# Current_Sense.net
KiCad netlist of a schematic drawn in Altium Designer
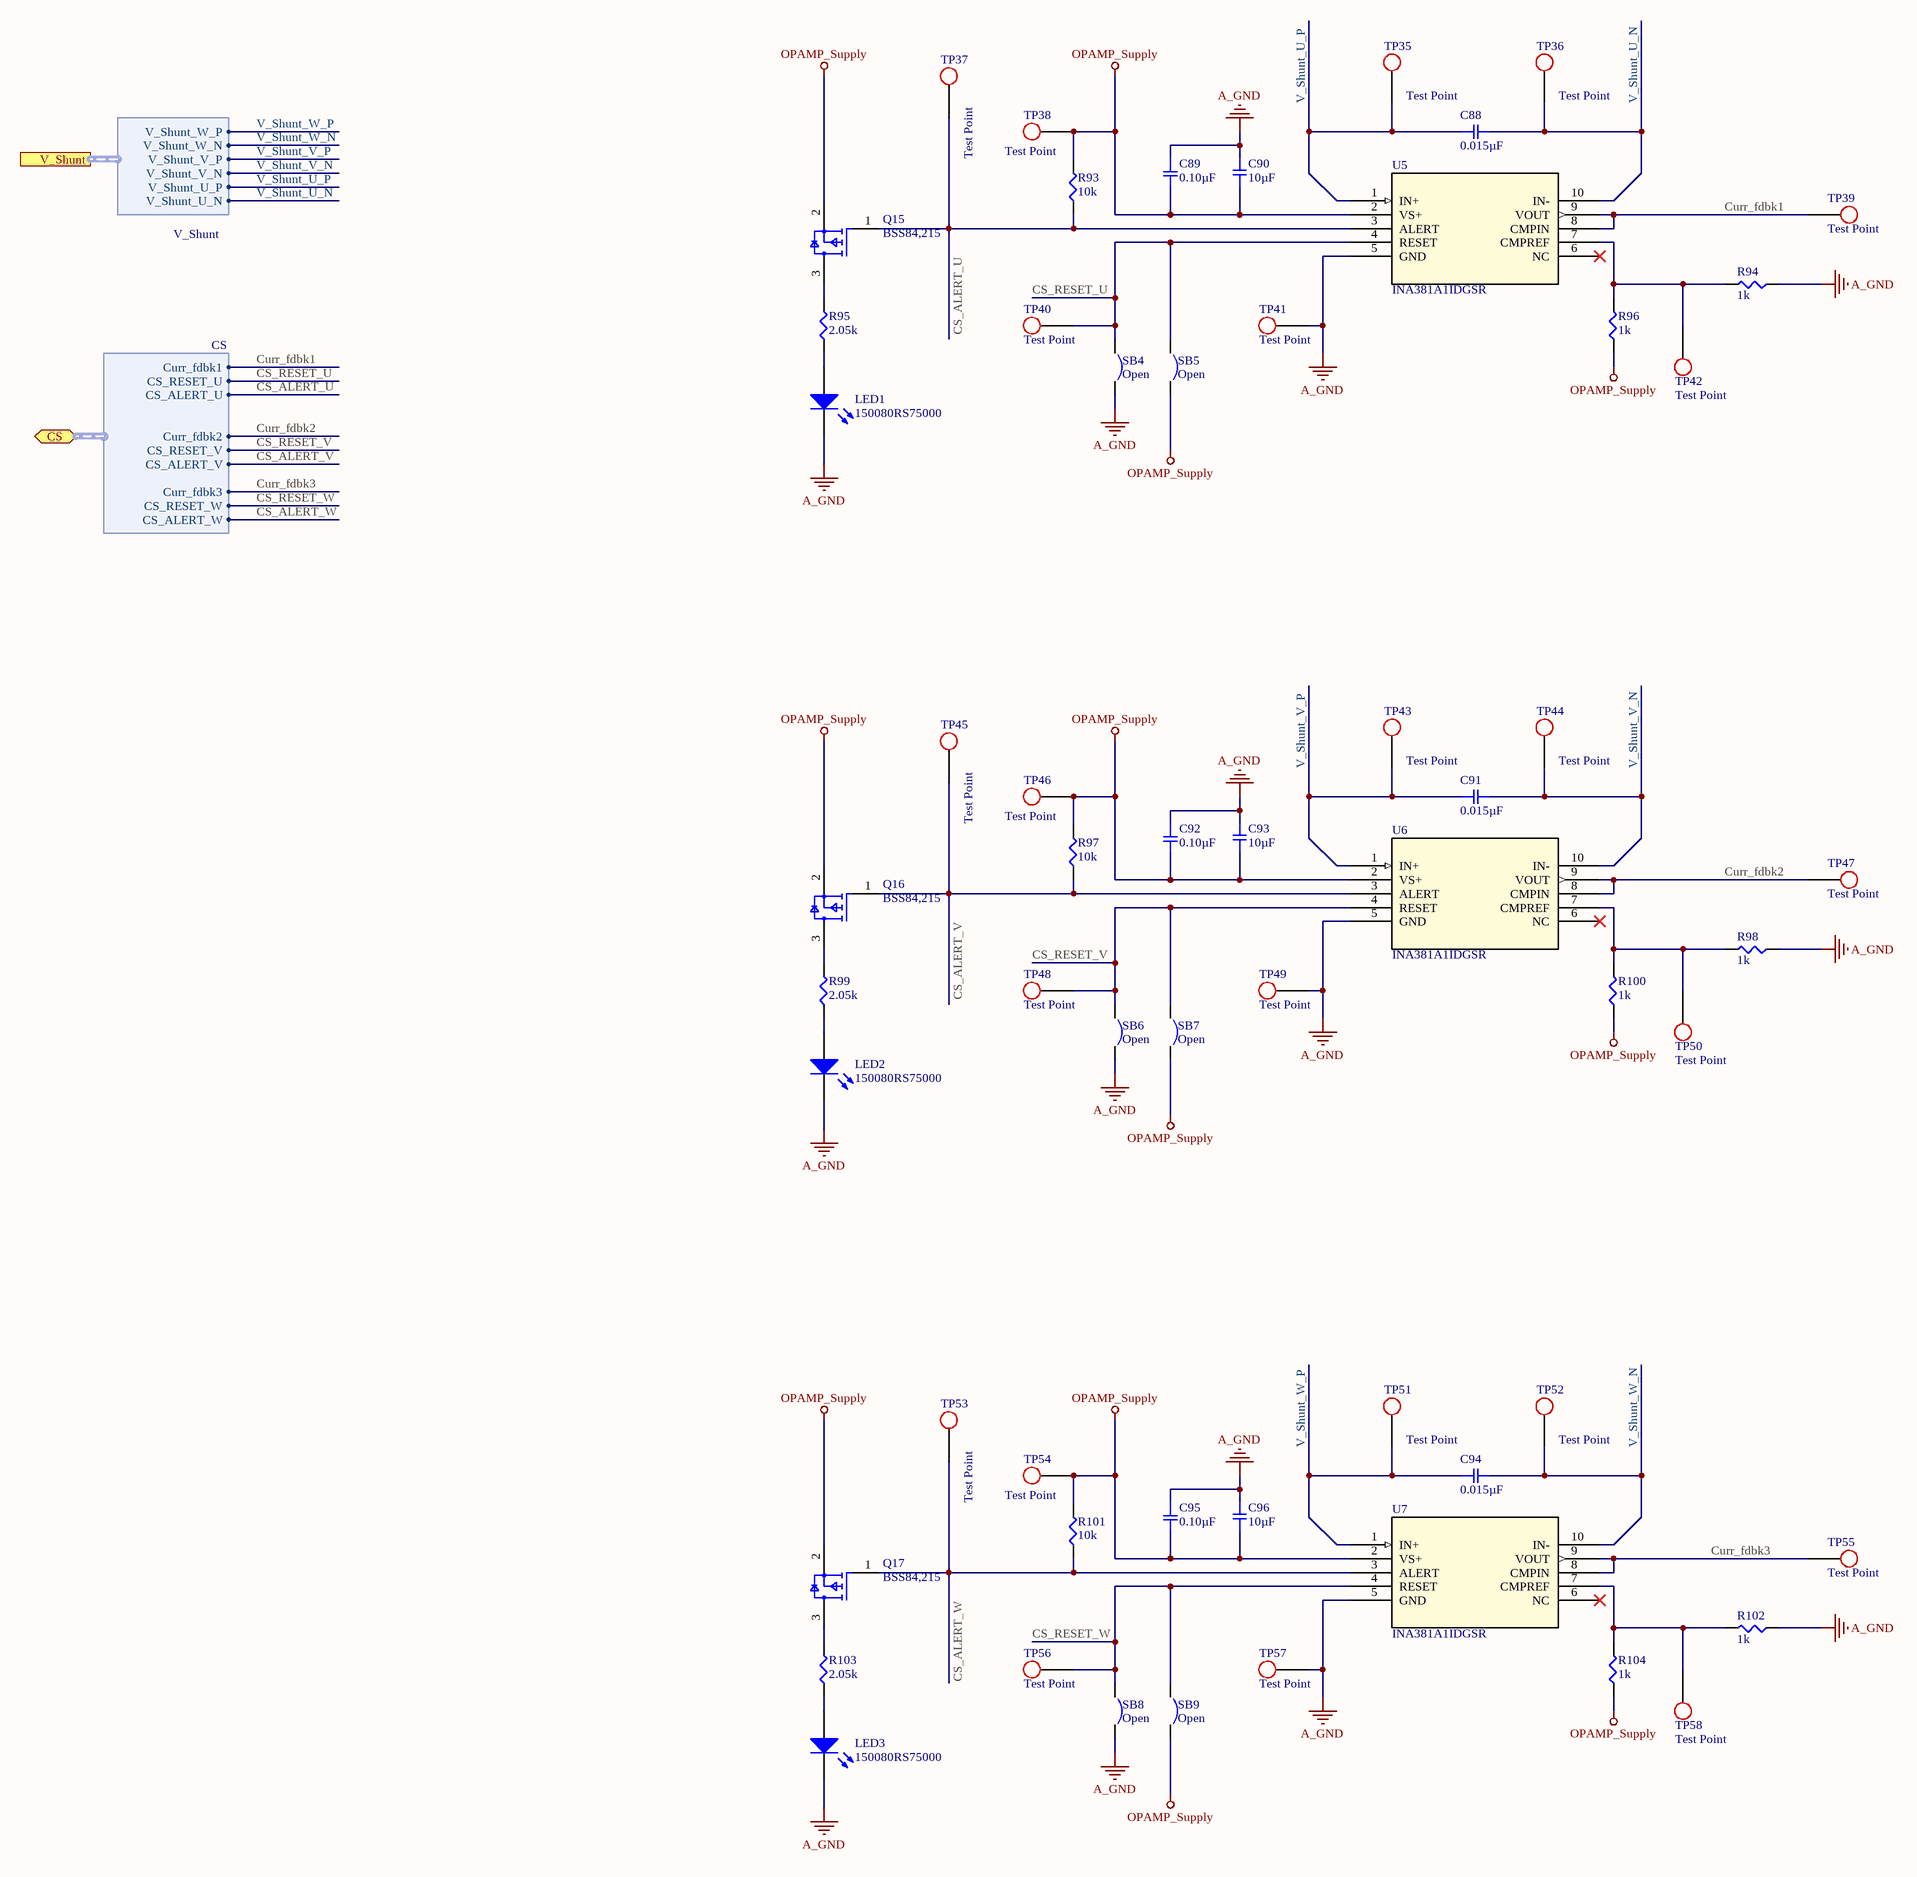
[diagram p0: Current Sense.SchDoc]

(export (version "E")
  (design (tool "Eeschema 10.0.6"))
  (components
    (comp (ref "C88")
      (value "0.015µF")
      (footprint "SMD-0603C")
      (description "CAP CER 0.015UF 100V X7R 0603")
      (fields
        (field (name "DIGI-KEY PART NUMBER") "490-5770-1-ND")
        (field (name "PART NUMBER") "GCJ188R72A153KA01D")
      )
      (libsource (lib "capacitor_murata_0603") (part "GCJ188R72A153KA01D"))
    )
    (comp (ref "C89")
      (value "0.10µF")
      (footprint "SMD-0805C")
      (description "CAP CER 0.1UF 50V X7R 0805")
      (fields
        (field (name "DIGI-KEY PART NUMBER") "490-8049-1-ND")
        (field (name "PART NUMBER") "GCM21BR71H104KA37K")
      )
      (libsource (lib "capacitor_murata_0805") (part "GCM21BR71H104KA37K"))
    )
    (comp (ref "C90")
      (value "10µF")
      (footprint "SMD-1206C")
      (description "CAP CER 10UF 25V X7R 1206")
      (fields
        (field (name "DIGI-KEY PART NUMBER") "490-10940-1-ND")
        (field (name "PART NUMBER") "GRJ31CR71E106KE11L")
      )
      (libsource (lib "capacitor_murata_1206") (part "GRJ31CR71E106KE11L"))
    )
    (comp (ref "C91")
      (value "0.015µF")
      (footprint "SMD-0603C")
      (description "CAP CER 0.015UF 100V X7R 0603")
      (fields
        (field (name "DIGI-KEY PART NUMBER") "490-5770-1-ND")
        (field (name "PART NUMBER") "GCJ188R72A153KA01D")
      )
      (libsource (lib "capacitor_murata_0603") (part "GCJ188R72A153KA01D"))
    )
    (comp (ref "C92")
      (value "0.10µF")
      (footprint "SMD-0805C")
      (description "CAP CER 0.1UF 50V X7R 0805")
      (fields
        (field (name "DIGI-KEY PART NUMBER") "490-8049-1-ND")
        (field (name "PART NUMBER") "GCM21BR71H104KA37K")
      )
      (libsource (lib "capacitor_murata_0805") (part "GCM21BR71H104KA37K"))
    )
    (comp (ref "C93")
      (value "10µF")
      (footprint "SMD-1206C")
      (description "CAP CER 10UF 25V X7R 1206")
      (fields
        (field (name "DIGI-KEY PART NUMBER") "490-10940-1-ND")
        (field (name "PART NUMBER") "GRJ31CR71E106KE11L")
      )
      (libsource (lib "capacitor_murata_1206") (part "GRJ31CR71E106KE11L"))
    )
    (comp (ref "C94")
      (value "0.015µF")
      (footprint "SMD-0603C")
      (description "CAP CER 0.015UF 100V X7R 0603")
      (fields
        (field (name "DIGI-KEY PART NUMBER") "490-5770-1-ND")
        (field (name "PART NUMBER") "GCJ188R72A153KA01D")
      )
      (libsource (lib "capacitor_murata_0603") (part "GCJ188R72A153KA01D"))
    )
    (comp (ref "C95")
      (value "0.10µF")
      (footprint "SMD-0805C")
      (description "CAP CER 0.1UF 50V X7R 0805")
      (fields
        (field (name "DIGI-KEY PART NUMBER") "490-8049-1-ND")
        (field (name "PART NUMBER") "GCM21BR71H104KA37K")
      )
      (libsource (lib "capacitor_murata_0805") (part "GCM21BR71H104KA37K"))
    )
    (comp (ref "C96")
      (value "10µF")
      (footprint "SMD-1206C")
      (description "CAP CER 10UF 25V X7R 1206")
      (fields
        (field (name "DIGI-KEY PART NUMBER") "490-10940-1-ND")
        (field (name "PART NUMBER") "GRJ31CR71E106KE11L")
      )
      (libsource (lib "capacitor_murata_1206") (part "GRJ31CR71E106KE11L"))
    )
    (comp (ref "LED1")
      (value "150080RS75000")
      (footprint "0805_A")
      (description "SMD mono-color Chip LED, WL-SMCW, Red")
      (libsource (lib "WL-SMCW SMD chip LED top view mono-color waterclear") (part "150080RS75000"))
    )
    (comp (ref "LED2")
      (value "150080RS75000")
      (footprint "0805_A")
      (description "SMD mono-color Chip LED, WL-SMCW, Red")
      (libsource (lib "WL-SMCW SMD chip LED top view mono-color waterclear") (part "150080RS75000"))
    )
    (comp (ref "LED3")
      (value "150080RS75000")
      (footprint "0805_A")
      (description "SMD mono-color Chip LED, WL-SMCW, Red")
      (libsource (lib "WL-SMCW SMD chip LED top view mono-color waterclear") (part "150080RS75000"))
    )
    (comp (ref "Q15")
      (value "BSS84,215")
      (footprint "FP-SOT23-MFG")
      (description "P-Channel 50V 130mA (Ta) 250mW (Tc) Surface Mount TO-236AB")
      (fields (field (name "OCTOPART") "https://octopart.com/bss84%2C215-nexperia-78739375"))
      (libsource (lib "Altium Content Vault") (part "2a9bca3c979204b206c86ddeb8c1a69"))
    )
    (comp (ref "Q16")
      (value "BSS84,215")
      (footprint "FP-SOT23-MFG")
      (description "P-Channel 50V 130mA (Ta) 250mW (Tc) Surface Mount TO-236AB")
      (fields (field (name "OCTOPART") "https://octopart.com/bss84%2C215-nexperia-78739375"))
      (libsource (lib "Altium Content Vault") (part "2a9bca3c979204b206c86ddeb8c1a69"))
    )
    (comp (ref "Q17")
      (value "BSS84,215")
      (footprint "FP-SOT23-MFG")
      (description "P-Channel 50V 130mA (Ta) 250mW (Tc) Surface Mount TO-236AB")
      (fields (field (name "OCTOPART") "https://octopart.com/bss84%2C215-nexperia-78739375"))
      (libsource (lib "Altium Content Vault") (part "2a9bca3c979204b206c86ddeb8c1a69"))
    )
    (comp (ref "R93")
      (value "10k")
      (footprint "SMD-0603-RES")
      (description "RES SMD 10K OHM 1% 1/10W 0603")
      (fields
        (field (name "PART NUMBER") "ERJ-3EKF1002V")
        (field (name "DIGI-KEY PART NUMBER") "P10.0KHCT-ND")
      )
      (libsource (lib "Panasonic_ERJ_0603") (part "ERJ-3EKF1002V"))
    )
    (comp (ref "R94")
      (value "1k")
      (footprint "SMD-0603-RES")
      (description "RES SMD 1K OHM 1% 1/10W 0603")
      (fields
        (field (name "PART NUMBER") "ERJ-3EKF1001V")
        (field (name "DIGI-KEY PART NUMBER") "P1.00KHCT-ND")
      )
      (libsource (lib "Panasonic_ERJ_0603") (part "ERJ-3EKF1001V"))
    )
    (comp (ref "R95")
      (value "2.05k")
      (footprint "SMD-0603-RES")
      (description "RES SMD 2.05K OHM 1% 1/10W 0603")
      (fields
        (field (name "PART NUMBER") "ERJ-3EKF2051V")
        (field (name "DIGI-KEY PART NUMBER") "P2.05KHCT-ND")
      )
      (libsource (lib "Panasonic_ERJ_0603") (part "ERJ-3EKF2051V"))
    )
    (comp (ref "R96")
      (value "1k")
      (footprint "SMD-0603-RES")
      (description "RES SMD 1K OHM 1% 1/10W 0603")
      (fields
        (field (name "PART NUMBER") "ERJ-3EKF1001V")
        (field (name "DIGI-KEY PART NUMBER") "P1.00KHCT-ND")
      )
      (libsource (lib "Panasonic_ERJ_0603") (part "ERJ-3EKF1001V"))
    )
    (comp (ref "R97")
      (value "10k")
      (footprint "SMD-0603-RES")
      (description "RES SMD 10K OHM 1% 1/10W 0603")
      (fields
        (field (name "PART NUMBER") "ERJ-3EKF1002V")
        (field (name "DIGI-KEY PART NUMBER") "P10.0KHCT-ND")
      )
      (libsource (lib "Panasonic_ERJ_0603") (part "ERJ-3EKF1002V"))
    )
    (comp (ref "R98")
      (value "1k")
      (footprint "SMD-0603-RES")
      (description "RES SMD 1K OHM 1% 1/10W 0603")
      (fields
        (field (name "PART NUMBER") "ERJ-3EKF1001V")
        (field (name "DIGI-KEY PART NUMBER") "P1.00KHCT-ND")
      )
      (libsource (lib "Panasonic_ERJ_0603") (part "ERJ-3EKF1001V"))
    )
    (comp (ref "R99")
      (value "2.05k")
      (footprint "SMD-0603-RES")
      (description "RES SMD 2.05K OHM 1% 1/10W 0603")
      (fields
        (field (name "PART NUMBER") "ERJ-3EKF2051V")
        (field (name "DIGI-KEY PART NUMBER") "P2.05KHCT-ND")
      )
      (libsource (lib "Panasonic_ERJ_0603") (part "ERJ-3EKF2051V"))
    )
    (comp (ref "R100")
      (value "1k")
      (footprint "SMD-0603-RES")
      (description "RES SMD 1K OHM 1% 1/10W 0603")
      (fields
        (field (name "PART NUMBER") "ERJ-3EKF1001V")
        (field (name "DIGI-KEY PART NUMBER") "P1.00KHCT-ND")
      )
      (libsource (lib "Panasonic_ERJ_0603") (part "ERJ-3EKF1001V"))
    )
    (comp (ref "R101")
      (value "10k")
      (footprint "SMD-0603-RES")
      (description "RES SMD 10K OHM 1% 1/10W 0603")
      (fields
        (field (name "PART NUMBER") "ERJ-3EKF1002V")
        (field (name "DIGI-KEY PART NUMBER") "P10.0KHCT-ND")
      )
      (libsource (lib "Panasonic_ERJ_0603") (part "ERJ-3EKF1002V"))
    )
    (comp (ref "R102")
      (value "1k")
      (footprint "SMD-0603-RES")
      (description "RES SMD 1K OHM 1% 1/10W 0603")
      (fields
        (field (name "PART NUMBER") "ERJ-3EKF1001V")
        (field (name "DIGI-KEY PART NUMBER") "P1.00KHCT-ND")
      )
      (libsource (lib "Panasonic_ERJ_0603") (part "ERJ-3EKF1001V"))
    )
    (comp (ref "R103")
      (value "2.05k")
      (footprint "SMD-0603-RES")
      (description "RES SMD 2.05K OHM 1% 1/10W 0603")
      (fields
        (field (name "PART NUMBER") "ERJ-3EKF2051V")
        (field (name "DIGI-KEY PART NUMBER") "P2.05KHCT-ND")
      )
      (libsource (lib "Panasonic_ERJ_0603") (part "ERJ-3EKF2051V"))
    )
    (comp (ref "R104")
      (value "1k")
      (footprint "SMD-0603-RES")
      (description "RES SMD 1K OHM 1% 1/10W 0603")
      (fields
        (field (name "PART NUMBER") "ERJ-3EKF1001V")
        (field (name "DIGI-KEY PART NUMBER") "P1.00KHCT-ND")
      )
      (libsource (lib "Panasonic_ERJ_0603") (part "ERJ-3EKF1001V"))
    )
    (comp (ref "SB4")
      (value "Open")
      (footprint "SB_0603")
      (description "Circuit Breaker")
      (fields (field (name "PUBLISHER") "Altium Limited"))
      (libsource (lib "NUCLEOG431RB-Custom-IN-A2212") (part "Solder Bridge"))
    )
    (comp (ref "SB5")
      (value "Open")
      (footprint "SB_0603")
      (description "Circuit Breaker")
      (fields (field (name "PUBLISHER") "Altium Limited"))
      (libsource (lib "NUCLEOG431RB-Custom-IN-A2212") (part "Solder Bridge"))
    )
    (comp (ref "SB6")
      (value "Open")
      (footprint "SB_0603")
      (description "Circuit Breaker")
      (fields (field (name "PUBLISHER") "Altium Limited"))
      (libsource (lib "NUCLEOG431RB-Custom-IN-A2212") (part "Solder Bridge"))
    )
    (comp (ref "SB7")
      (value "Open")
      (footprint "SB_0603")
      (description "Circuit Breaker")
      (fields (field (name "PUBLISHER") "Altium Limited"))
      (libsource (lib "NUCLEOG431RB-Custom-IN-A2212") (part "Solder Bridge"))
    )
    (comp (ref "SB8")
      (value "Open")
      (footprint "SB_0603")
      (description "Circuit Breaker")
      (fields (field (name "PUBLISHER") "Altium Limited"))
      (libsource (lib "NUCLEOG431RB-Custom-IN-A2212") (part "Solder Bridge"))
    )
    (comp (ref "SB9")
      (value "Open")
      (footprint "SB_0603")
      (description "Circuit Breaker")
      (fields (field (name "PUBLISHER") "Altium Limited"))
      (libsource (lib "NUCLEOG431RB-Custom-IN-A2212") (part "Solder Bridge"))
    )
    (comp (ref "TP35")
      (value "Test Point")
      (footprint "Test_point_THT")
      (libsource (lib "Power Board UCC28951") (part "Test Point"))
    )
    (comp (ref "TP36")
      (value "Test Point")
      (footprint "Test_point_THT")
      (libsource (lib "Power Board UCC28951") (part "Test Point"))
    )
    (comp (ref "TP37")
      (value "Test Point")
      (footprint "Test_point_THT")
      (libsource (lib "Power Board UCC28951") (part "Test Point"))
    )
    (comp (ref "TP38")
      (value "Test Point")
      (footprint "Test_point_SMD")
      (libsource (lib "NUCLEOG431RB-Custom-IN-A2212") (part "Test Point"))
    )
    (comp (ref "TP39")
      (value "Test Point")
      (footprint "Test_point_THT")
      (libsource (lib "Power Board UCC28951") (part "Test Point"))
    )
    (comp (ref "TP40")
      (value "Test Point")
      (footprint "Test_point_SMD")
      (libsource (lib "NUCLEOG431RB-Custom-IN-A2212") (part "Test Point"))
    )
    (comp (ref "TP41")
      (value "Test Point")
      (footprint "Test_point_THT")
      (libsource (lib "Power Board UCC28951") (part "Test Point"))
    )
    (comp (ref "TP42")
      (value "Test Point")
      (footprint "Test_point_THT")
      (libsource (lib "NUCLEOG431RB-Custom-IN-A2212") (part "Test Point"))
    )
    (comp (ref "TP43")
      (value "Test Point")
      (footprint "Test_point_THT")
      (libsource (lib "Power Board UCC28951") (part "Test Point"))
    )
    (comp (ref "TP44")
      (value "Test Point")
      (footprint "Test_point_THT")
      (libsource (lib "Power Board UCC28951") (part "Test Point"))
    )
    (comp (ref "TP45")
      (value "Test Point")
      (footprint "Test_point_THT")
      (libsource (lib "Power Board UCC28951") (part "Test Point"))
    )
    (comp (ref "TP46")
      (value "Test Point")
      (footprint "Test_point_SMD")
      (libsource (lib "NUCLEOG431RB-Custom-IN-A2212") (part "Test Point"))
    )
    (comp (ref "TP47")
      (value "Test Point")
      (footprint "Test_point_THT")
      (libsource (lib "Power Board UCC28951") (part "Test Point"))
    )
    (comp (ref "TP48")
      (value "Test Point")
      (footprint "Test_point_SMD")
      (libsource (lib "NUCLEOG431RB-Custom-IN-A2212") (part "Test Point"))
    )
    (comp (ref "TP49")
      (value "Test Point")
      (footprint "Test_point_THT")
      (libsource (lib "Power Board UCC28951") (part "Test Point"))
    )
    (comp (ref "TP50")
      (value "Test Point")
      (footprint "Test_point_THT")
      (libsource (lib "NUCLEOG431RB-Custom-IN-A2212") (part "Test Point"))
    )
    (comp (ref "TP51")
      (value "Test Point")
      (footprint "Test_point_THT")
      (libsource (lib "Power Board UCC28951") (part "Test Point"))
    )
    (comp (ref "TP52")
      (value "Test Point")
      (footprint "Test_point_THT")
      (libsource (lib "Power Board UCC28951") (part "Test Point"))
    )
    (comp (ref "TP53")
      (value "Test Point")
      (footprint "Test_point_THT")
      (libsource (lib "Power Board UCC28951") (part "Test Point"))
    )
    (comp (ref "TP54")
      (value "Test Point")
      (footprint "Test_point_SMD")
      (libsource (lib "NUCLEOG431RB-Custom-IN-A2212") (part "Test Point"))
    )
    (comp (ref "TP55")
      (value "Test Point")
      (footprint "Test_point_THT")
      (libsource (lib "Power Board UCC28951") (part "Test Point"))
    )
    (comp (ref "TP56")
      (value "Test Point")
      (footprint "Test_point_SMD")
      (libsource (lib "NUCLEOG431RB-Custom-IN-A2212") (part "Test Point"))
    )
    (comp (ref "TP57")
      (value "Test Point")
      (footprint "Test_point_THT")
      (libsource (lib "Power Board UCC28951") (part "Test Point"))
    )
    (comp (ref "TP58")
      (value "Test Point")
      (footprint "Test_point_THT")
      (libsource (lib "NUCLEOG431RB-Custom-IN-A2212") (part "Test Point"))
    )
    (comp (ref "U5")
      (value "INA381A1IDGSR")
      (footprint "TSSOP50P490X110-10N")
      (description "No Description Available")
      (fields (field (name "COPYRIGHT") "Copyright (C) 2018 Accelerated Designs. All rights reserved"))
      (libsource (lib "NUCLEOG431RB-Custom-IN-A2212") (part "INA381A1IDGSR"))
    )
    (comp (ref "U6")
      (value "INA381A1IDGSR")
      (footprint "TSSOP50P490X110-10N")
      (description "No Description Available")
      (fields (field (name "COPYRIGHT") "Copyright (C) 2018 Accelerated Designs. All rights reserved"))
      (libsource (lib "NUCLEOG431RB-Custom-IN-A2212") (part "INA381A1IDGSR"))
    )
    (comp (ref "U7")
      (value "INA381A1IDGSR")
      (footprint "TSSOP50P490X110-10N")
      (description "No Description Available")
      (fields (field (name "COPYRIGHT") "Copyright (C) 2018 Accelerated Designs. All rights reserved"))
      (libsource (lib "NUCLEOG431RB-Custom-IN-A2212") (part "INA381A1IDGSR"))
    )
  )
  (nets
    (net (code "3") (name "/CS_ALERT_U") (class "Default")
      (node (ref "Q15") (pin "1") (pinfunction "G_1") (pintype "passive"))
      (node (ref "R93") (pin "1") (pinfunction "1_1") (pintype "passive"))
      (node (ref "TP37") (pin "1") (pinfunction "1_1") (pintype "passive"))
      (node (ref "U5") (pin "3") (pinfunction "ALERT_3") (pintype "passive"))
    )
    (net (code "4") (name "/CS_ALERT_V") (class "Default")
      (node (ref "Q16") (pin "1") (pinfunction "G_1") (pintype "passive"))
      (node (ref "R97") (pin "1") (pinfunction "1_1") (pintype "passive"))
      (node (ref "TP45") (pin "1") (pinfunction "1_1") (pintype "passive"))
      (node (ref "U6") (pin "3") (pinfunction "ALERT_3") (pintype "passive"))
    )
    (net (code "5") (name "/CS_ALERT_W") (class "Default")
      (node (ref "Q17") (pin "1") (pinfunction "G_1") (pintype "passive"))
      (node (ref "R101") (pin "1") (pinfunction "1_1") (pintype "passive"))
      (node (ref "TP53") (pin "1") (pinfunction "1_1") (pintype "passive"))
      (node (ref "U7") (pin "3") (pinfunction "ALERT_3") (pintype "passive"))
    )
    (net (code "6") (name "/CS_RESET_U") (class "Default")
      (node (ref "SB4") (pin "2") (pinfunction "2_2") (pintype "passive"))
      (node (ref "SB5") (pin "2") (pinfunction "2_2") (pintype "passive"))
      (node (ref "TP40") (pin "1") (pinfunction "1_1") (pintype "passive"))
      (node (ref "U5") (pin "4") (pinfunction "RESET_4") (pintype "passive"))
    )
    (net (code "7") (name "/CS_RESET_V") (class "Default")
      (node (ref "SB6") (pin "2") (pinfunction "2_2") (pintype "passive"))
      (node (ref "SB7") (pin "2") (pinfunction "2_2") (pintype "passive"))
      (node (ref "TP48") (pin "1") (pinfunction "1_1") (pintype "passive"))
      (node (ref "U6") (pin "4") (pinfunction "RESET_4") (pintype "passive"))
    )
    (net (code "8") (name "/CS_RESET_W") (class "Default")
      (node (ref "SB8") (pin "2") (pinfunction "2_2") (pintype "passive"))
      (node (ref "SB9") (pin "2") (pinfunction "2_2") (pintype "passive"))
      (node (ref "TP56") (pin "1") (pinfunction "1_1") (pintype "passive"))
      (node (ref "U7") (pin "4") (pinfunction "RESET_4") (pintype "passive"))
    )
    (net (code "9") (name "/Curr_fdbk1") (class "Default")
      (node (ref "TP39") (pin "1") (pinfunction "1_1") (pintype "passive"))
      (node (ref "U5") (pin "8") (pinfunction "CMPIN_8") (pintype "passive"))
      (node (ref "U5") (pin "9") (pinfunction "VOUT_9") (pintype "output"))
    )
    (net (code "10") (name "/Curr_fdbk2") (class "Default")
      (node (ref "TP47") (pin "1") (pinfunction "1_1") (pintype "passive"))
      (node (ref "U6") (pin "8") (pinfunction "CMPIN_8") (pintype "passive"))
      (node (ref "U6") (pin "9") (pinfunction "VOUT_9") (pintype "output"))
    )
    (net (code "11") (name "/Curr_fdbk3") (class "Default")
      (node (ref "TP55") (pin "1") (pinfunction "1_1") (pintype "passive"))
      (node (ref "U7") (pin "8") (pinfunction "CMPIN_8") (pintype "passive"))
      (node (ref "U7") (pin "9") (pinfunction "VOUT_9") (pintype "output"))
    )
    (net (code "12") (name "/V_Shunt_U_N") (class "Default")
      (node (ref "C88") (pin "2") (pinfunction "2_2") (pintype "passive"))
      (node (ref "TP36") (pin "1") (pinfunction "1_1") (pintype "passive"))
      (node (ref "U5") (pin "10") (pinfunction "IN-_10") (pintype "passive"))
    )
    (net (code "13") (name "/V_Shunt_U_P") (class "Default")
      (node (ref "C88") (pin "1") (pinfunction "1_1") (pintype "passive"))
      (node (ref "TP35") (pin "1") (pinfunction "1_1") (pintype "passive"))
      (node (ref "U5") (pin "1") (pinfunction "IN+_1") (pintype "input"))
    )
    (net (code "14") (name "/V_Shunt_V_N") (class "Default")
      (node (ref "C91") (pin "2") (pinfunction "2_2") (pintype "passive"))
      (node (ref "TP44") (pin "1") (pinfunction "1_1") (pintype "passive"))
      (node (ref "U6") (pin "10") (pinfunction "IN-_10") (pintype "passive"))
    )
    (net (code "15") (name "/V_Shunt_V_P") (class "Default")
      (node (ref "C91") (pin "1") (pinfunction "1_1") (pintype "passive"))
      (node (ref "TP43") (pin "1") (pinfunction "1_1") (pintype "passive"))
      (node (ref "U6") (pin "1") (pinfunction "IN+_1") (pintype "input"))
    )
    (net (code "16") (name "/V_Shunt_W_N") (class "Default")
      (node (ref "C94") (pin "2") (pinfunction "2_2") (pintype "passive"))
      (node (ref "TP52") (pin "1") (pinfunction "1_1") (pintype "passive"))
      (node (ref "U7") (pin "10") (pinfunction "IN-_10") (pintype "passive"))
    )
    (net (code "17") (name "/V_Shunt_W_P") (class "Default")
      (node (ref "C94") (pin "1") (pinfunction "1_1") (pintype "passive"))
      (node (ref "TP51") (pin "1") (pinfunction "1_1") (pintype "passive"))
      (node (ref "U7") (pin "1") (pinfunction "IN+_1") (pintype "input"))
    )
    (net (code "20") (name "A_GND") (class "Default")
      (node (ref "C89") (pin "1") (pinfunction "1_1") (pintype "passive"))
      (node (ref "C90") (pin "2") (pinfunction "2_2") (pintype "passive"))
      (node (ref "C92") (pin "1") (pinfunction "1_1") (pintype "passive"))
      (node (ref "C93") (pin "2") (pinfunction "2_2") (pintype "passive"))
      (node (ref "C95") (pin "1") (pinfunction "1_1") (pintype "passive"))
      (node (ref "C96") (pin "2") (pinfunction "2_2") (pintype "passive"))
      (node (ref "LED1") (pin "1") (pinfunction "K_1") (pintype "passive"))
      (node (ref "LED2") (pin "1") (pinfunction "K_1") (pintype "passive"))
      (node (ref "LED3") (pin "1") (pinfunction "K_1") (pintype "passive"))
      (node (ref "R102") (pin "1") (pinfunction "1_1") (pintype "passive"))
      (node (ref "R94") (pin "1") (pinfunction "1_1") (pintype "passive"))
      (node (ref "R98") (pin "1") (pinfunction "1_1") (pintype "passive"))
      (node (ref "SB4") (pin "1") (pinfunction "1_1") (pintype "passive"))
      (node (ref "SB6") (pin "1") (pinfunction "1_1") (pintype "passive"))
      (node (ref "SB8") (pin "1") (pinfunction "1_1") (pintype "passive"))
      (node (ref "TP41") (pin "1") (pinfunction "1_1") (pintype "passive"))
      (node (ref "TP49") (pin "1") (pinfunction "1_1") (pintype "passive"))
      (node (ref "TP57") (pin "1") (pinfunction "1_1") (pintype "passive"))
      (node (ref "U5") (pin "5") (pinfunction "GND_5") (pintype "passive"))
      (node (ref "U6") (pin "5") (pinfunction "GND_5") (pintype "passive"))
      (node (ref "U7") (pin "5") (pinfunction "GND_5") (pintype "passive"))
    )
    (net (code "21") (name "Net-(LED1-A)") (class "Default")
      (node (ref "LED1") (pin "2") (pinfunction "A_2") (pintype "passive"))
      (node (ref "R95") (pin "1") (pinfunction "1_1") (pintype "passive"))
    )
    (net (code "22") (name "Net-(LED2-A)") (class "Default")
      (node (ref "LED2") (pin "2") (pinfunction "A_2") (pintype "passive"))
      (node (ref "R99") (pin "1") (pinfunction "1_1") (pintype "passive"))
    )
    (net (code "23") (name "Net-(LED3-A)") (class "Default")
      (node (ref "LED3") (pin "2") (pinfunction "A_2") (pintype "passive"))
      (node (ref "R103") (pin "1") (pinfunction "1_1") (pintype "passive"))
    )
    (net (code "24") (name "Net-(Q15-D)") (class "Default")
      (node (ref "Q15") (pin "3") (pinfunction "D_3") (pintype "passive"))
      (node (ref "R95") (pin "2") (pinfunction "2_2") (pintype "passive"))
    )
    (net (code "25") (name "Net-(Q16-D)") (class "Default")
      (node (ref "Q16") (pin "3") (pinfunction "D_3") (pintype "passive"))
      (node (ref "R99") (pin "2") (pinfunction "2_2") (pintype "passive"))
    )
    (net (code "26") (name "Net-(Q17-D)") (class "Default")
      (node (ref "Q17") (pin "3") (pinfunction "D_3") (pintype "passive"))
      (node (ref "R103") (pin "2") (pinfunction "2_2") (pintype "passive"))
    )
    (net (code "27") (name "Net-(U5-CMPREF)") (class "Default")
      (node (ref "R94") (pin "2") (pinfunction "2_2") (pintype "passive"))
      (node (ref "R96") (pin "2") (pinfunction "2_2") (pintype "passive"))
      (node (ref "TP42") (pin "1") (pinfunction "1_1") (pintype "passive"))
      (node (ref "U5") (pin "7") (pinfunction "CMPREF_7") (pintype "passive"))
    )
    (net (code "28") (name "Net-(U6-CMPREF)") (class "Default")
      (node (ref "R100") (pin "2") (pinfunction "2_2") (pintype "passive"))
      (node (ref "R98") (pin "2") (pinfunction "2_2") (pintype "passive"))
      (node (ref "TP50") (pin "1") (pinfunction "1_1") (pintype "passive"))
      (node (ref "U6") (pin "7") (pinfunction "CMPREF_7") (pintype "passive"))
    )
    (net (code "29") (name "Net-(U7-CMPREF)") (class "Default")
      (node (ref "R102") (pin "2") (pinfunction "2_2") (pintype "passive"))
      (node (ref "R104") (pin "2") (pinfunction "2_2") (pintype "passive"))
      (node (ref "TP58") (pin "1") (pinfunction "1_1") (pintype "passive"))
      (node (ref "U7") (pin "7") (pinfunction "CMPREF_7") (pintype "passive"))
    )
    (net (code "30") (name "OPAMP_Supply") (class "Default")
      (node (ref "C89") (pin "2") (pinfunction "2_2") (pintype "passive"))
      (node (ref "C90") (pin "1") (pinfunction "1_1") (pintype "passive"))
      (node (ref "C92") (pin "2") (pinfunction "2_2") (pintype "passive"))
      (node (ref "C93") (pin "1") (pinfunction "1_1") (pintype "passive"))
      (node (ref "C95") (pin "2") (pinfunction "2_2") (pintype "passive"))
      (node (ref "C96") (pin "1") (pinfunction "1_1") (pintype "passive"))
      (node (ref "Q15") (pin "2") (pinfunction "S_2") (pintype "passive"))
      (node (ref "Q16") (pin "2") (pinfunction "S_2") (pintype "passive"))
      (node (ref "Q17") (pin "2") (pinfunction "S_2") (pintype "passive"))
      (node (ref "R100") (pin "1") (pinfunction "1_1") (pintype "passive"))
      (node (ref "R101") (pin "2") (pinfunction "2_2") (pintype "passive"))
      (node (ref "R104") (pin "1") (pinfunction "1_1") (pintype "passive"))
      (node (ref "R93") (pin "2") (pinfunction "2_2") (pintype "passive"))
      (node (ref "R96") (pin "1") (pinfunction "1_1") (pintype "passive"))
      (node (ref "R97") (pin "2") (pinfunction "2_2") (pintype "passive"))
      (node (ref "SB5") (pin "1") (pinfunction "1_1") (pintype "passive"))
      (node (ref "SB7") (pin "1") (pinfunction "1_1") (pintype "passive"))
      (node (ref "SB9") (pin "1") (pinfunction "1_1") (pintype "passive"))
      (node (ref "TP38") (pin "1") (pinfunction "1_1") (pintype "passive"))
      (node (ref "TP46") (pin "1") (pinfunction "1_1") (pintype "passive"))
      (node (ref "TP54") (pin "1") (pinfunction "1_1") (pintype "passive"))
      (node (ref "U5") (pin "2") (pinfunction "VS+_2") (pintype "passive"))
      (node (ref "U6") (pin "2") (pinfunction "VS+_2") (pintype "passive"))
      (node (ref "U7") (pin "2") (pinfunction "VS+_2") (pintype "passive"))
    )
    (net (code "31") (name "unconnected-(U5-NC-Pad6)") (class "Default")
      (node (ref "U5") (pin "6") (pinfunction "NC_6") (pintype "passive+no_connect"))
    )
    (net (code "32") (name "unconnected-(U6-NC-Pad6)") (class "Default")
      (node (ref "U6") (pin "6") (pinfunction "NC_6") (pintype "passive+no_connect"))
    )
    (net (code "33") (name "unconnected-(U7-NC-Pad6)") (class "Default")
      (node (ref "U7") (pin "6") (pinfunction "NC_6") (pintype "passive+no_connect"))
    )
  )
)
